# MCU152A_USB_and_Power.net
KiCad netlist of a schematic drawn in Altium Designer
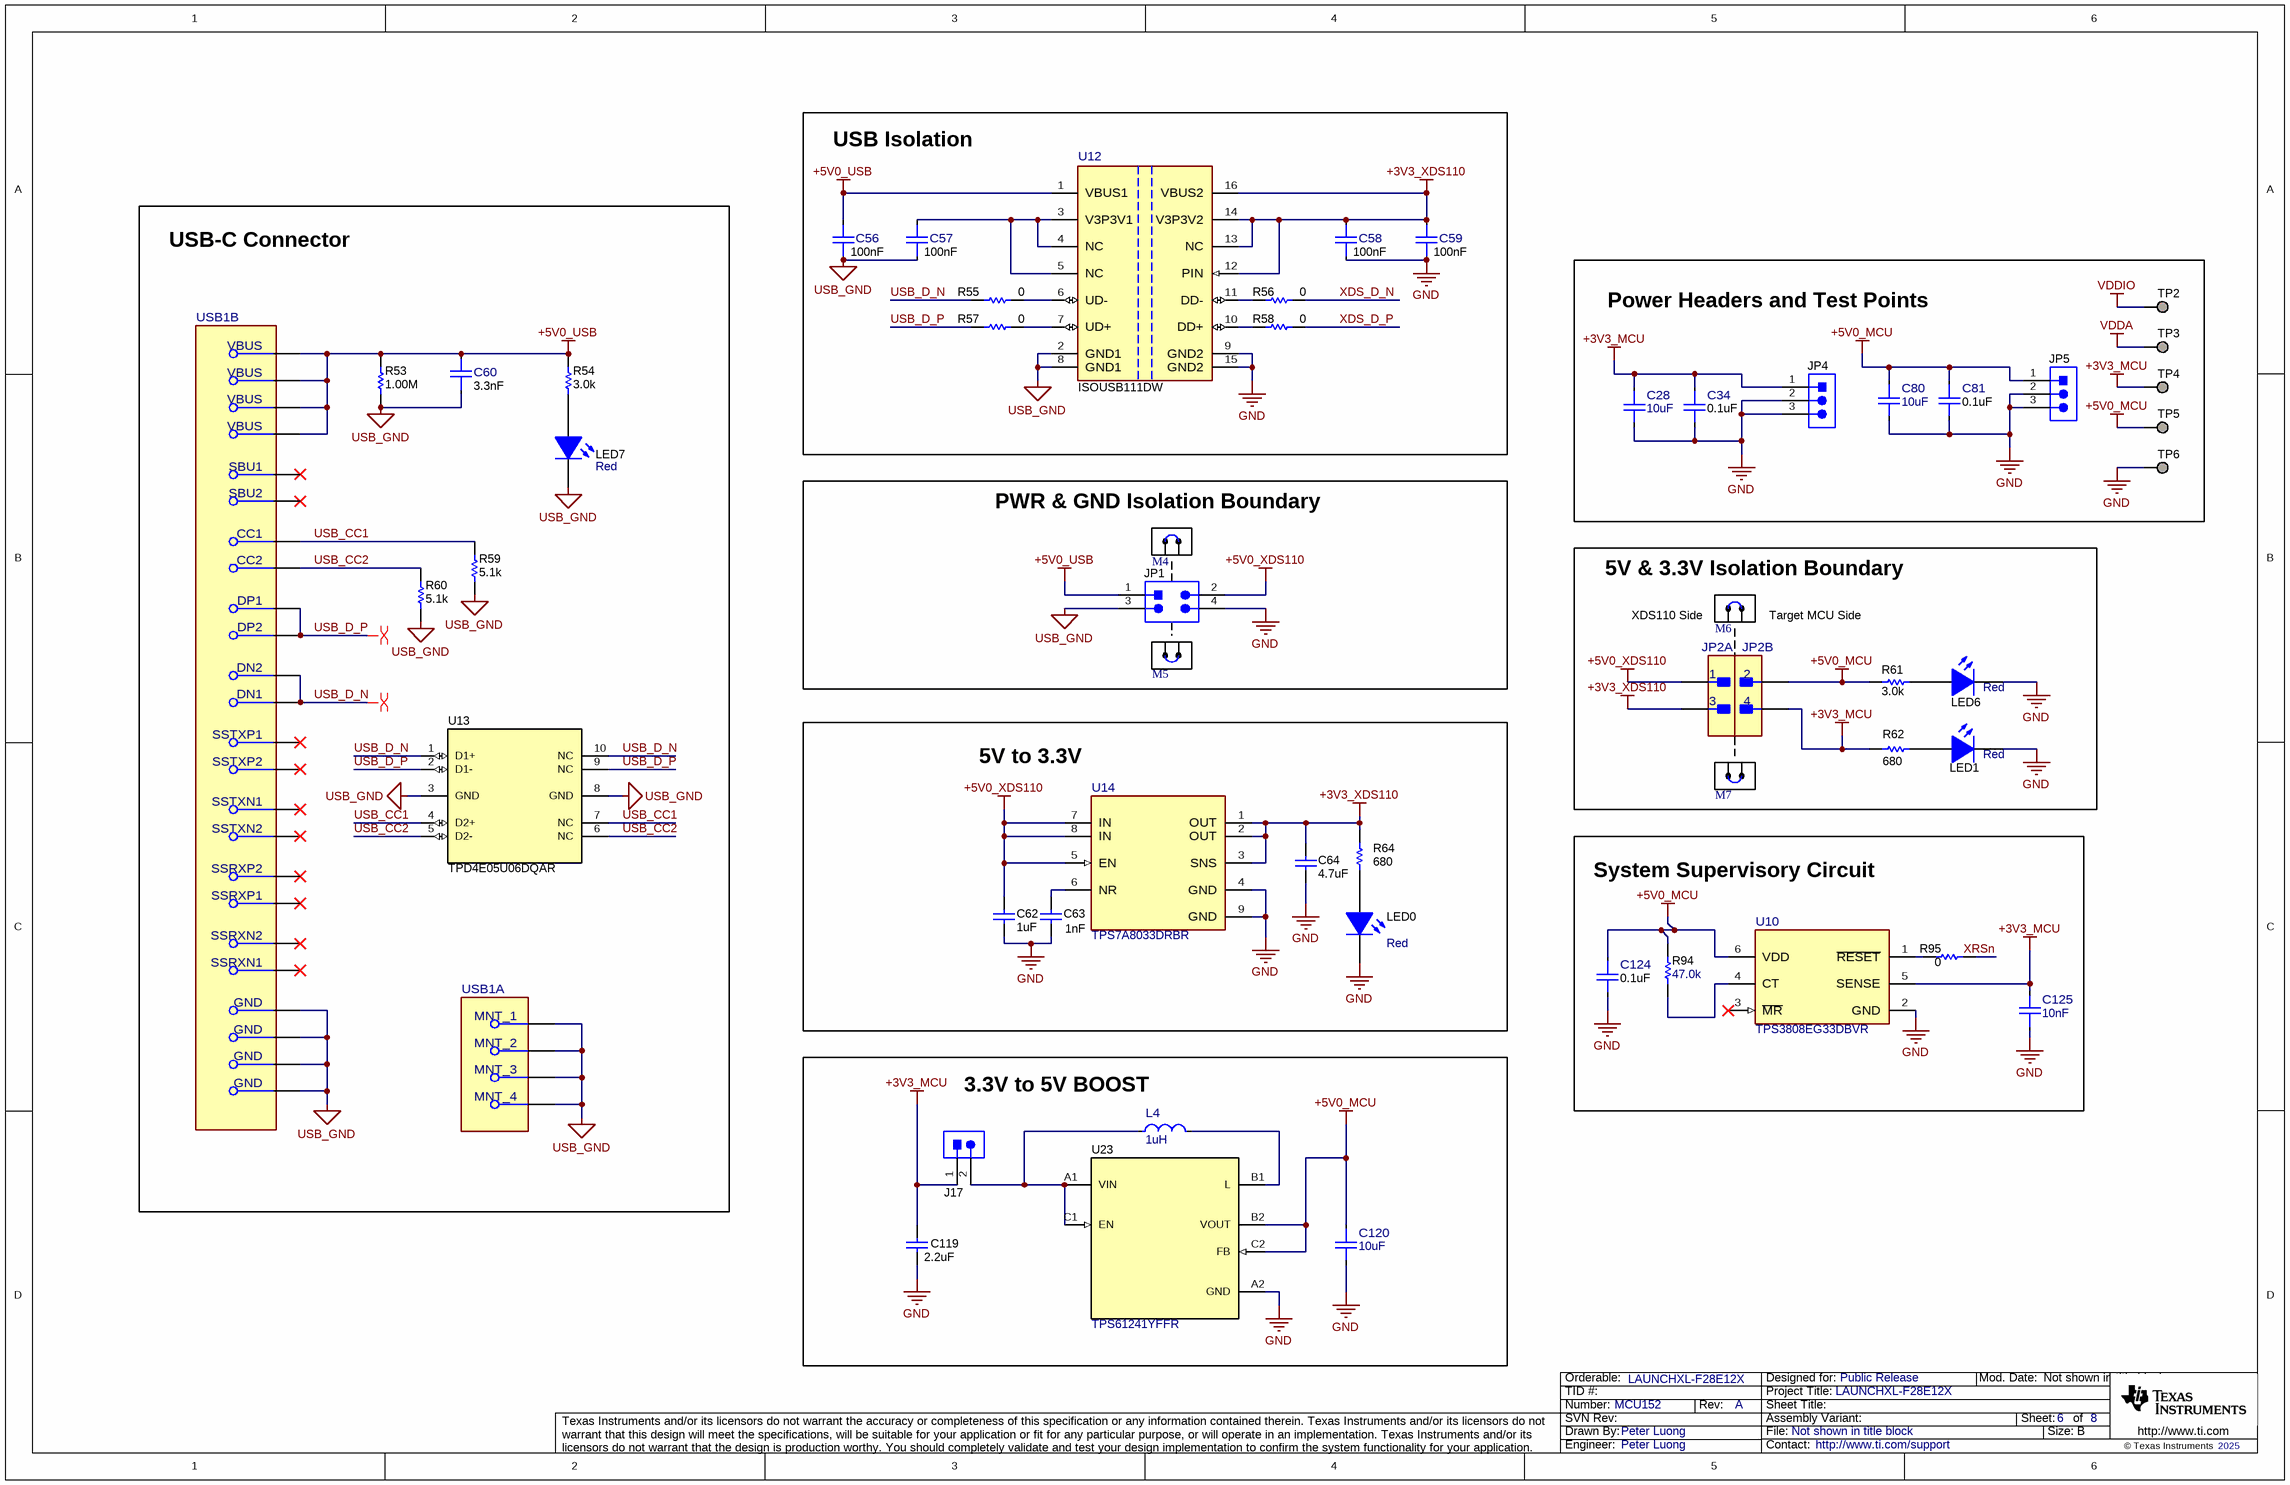
[diagram p0: MCU152A_USB_and_Power.SchDoc]

(export (version "E")
  (design (tool "Eeschema 10.0.6"))
  (components
    (comp (ref "C28")
      (value "885012106031")
      (footprint "FP-885012106031_0603-MFG")
      (description "10 µF ±20% 25V Ceramic Capacitor X5R 0603 (1608 Metric)")
      (fields (field (name "MANUFACTURER") "Wurth") (field (name "VALUEDISPLAYED") "10uF"))
      (libsource (lib "Altium Vault - TI") (part "SYM-885012106031"))
    )
    (comp (ref "C34")
      (value "885012205018")
      (footprint "FP-885012205018_0402-MFG")
      (description "0.1µF ±10% 10V Ceramic Capacitor X7R 0402 (1005 Metric)")
      (fields
        (field (name "MANUFACTURER") "Wurth Electronics")
        (field (name "MOUSER PART NUMBER") "710-885012205018")
        (field (name "VALUEDISPLAYED") "0.1uF")
      )
      (libsource (lib "Altium Vault - TI") (part "SYM-885012205018"))
    )
    (comp (ref "C56")
      (value "885012205018")
      (footprint "FP-885012205018_0402-MFG")
      (description "0.1µF ±10% 10V Ceramic Capacitor X7R 0402 (1005 Metric)")
      (fields
        (field (name "MANUFACTURER") "Wurth Electronics")
        (field (name "MOUSER PART NUMBER") "710-885012205018")
        (field (name "CAP_F") "100nF")
      )
      (libsource (lib "Altium Vault - TI") (part "SYM-885012205018"))
    )
    (comp (ref "C57")
      (value "885012205018")
      (footprint "FP-885012205018_0402-MFG")
      (description "0.1µF ±10% 10V Ceramic Capacitor X7R 0402 (1005 Metric)")
      (fields
        (field (name "MANUFACTURER") "Wurth Electronics")
        (field (name "MOUSER PART NUMBER") "710-885012205018")
        (field (name "CAP_F") "100nF")
      )
      (libsource (lib "Altium Vault - TI") (part "SYM-885012205018"))
    )
    (comp (ref "C58")
      (value "885012205018")
      (footprint "FP-885012205018_0402-MFG")
      (description "0.1µF ±10% 10V Ceramic Capacitor X7R 0402 (1005 Metric)")
      (fields
        (field (name "MANUFACTURER") "Wurth Electronics")
        (field (name "MOUSER PART NUMBER") "710-885012205018")
        (field (name "CAP_F") "100nF")
      )
      (libsource (lib "Altium Vault - TI") (part "SYM-885012205018"))
    )
    (comp (ref "C59")
      (value "885012205018")
      (footprint "FP-885012205018_0402-MFG")
      (description "0.1µF ±10% 10V Ceramic Capacitor X7R 0402 (1005 Metric)")
      (fields
        (field (name "MANUFACTURER") "Wurth Electronics")
        (field (name "MOUSER PART NUMBER") "710-885012205018")
        (field (name "CAP_F") "100nF")
      )
      (libsource (lib "Altium Vault - TI") (part "SYM-885012205018"))
    )
    (comp (ref "C60")
      (value "885012205064")
      (footprint "FP-885012205064_0402-MFG")
      (description "Cap Cer 3300pF 50V X7R 0402")
      (fields
        (field (name "MANUFACTURER") "Wurth Electronics")
        (field (name "DIGIKEY PART NUMBER") "732-7559-1-ND")
        (field (name "VALUEDISPLAYED") "3.3nF")
      )
      (libsource (lib "Altium Vault - TI") (part "SYM-885012205064"))
    )
    (comp (ref "C62")
      (value "885012105012")
      (footprint "0402")
      (description "CAP, CERM, 1 uF, 10 V,+/- 20%, X5R, 0402")
      (fields
        (field (name "VALUEDISPLAYED") "1uF")
        (field (name "MANUFACTURER") "Wurth Elektronik")
        (field (name "PUBLISHER") "Texas Instruments")
      )
      (libsource (lib "Altium Vault - TI") (part "Capacitor"))
    )
    (comp (ref "C63")
      (value "885012205061")
      (footprint "0402")
      (description "CAP, CERM, 1000 pF, 50 V, +/- 10%, X7R, 0402")
      (fields
        (field (name "MANUFACTURER") "Wurth Elektronik")
        (field (name "CAP_F") "1nF")
        (field (name "PUBLISHER") "Texas Instruments")
      )
      (libsource (lib "Altium Vault - TI") (part "Capacitor"))
    )
    (comp (ref "C64")
      (value "C1005X5R1A475K050BC")
      (footprint "0402_065")
      (description "CAP, CERM, 4.7 uF, 10 V, +/- 10%, X5R, 0402")
      (fields
        (field (name "MANUFACTURER") "TDK")
        (field (name "VALUEDISPLAYED") "4.7uF")
        (field (name "PUBLISHER") "Texas Instruments")
      )
      (libsource (lib "Altium Vault - TI") (part "Capacitor"))
    )
    (comp (ref "C80")
      (value "885012106031")
      (footprint "FP-885012106031_0603-MFG")
      (description "10 µF ±20% 25V Ceramic Capacitor X5R 0603 (1608 Metric)")
      (fields (field (name "MANUFACTURER") "Wurth") (field (name "VALUEDISPLAYED") "10uF"))
      (libsource (lib "Altium Vault - TI") (part "SYM-885012106031"))
    )
    (comp (ref "C81")
      (value "885012205018")
      (footprint "FP-885012205018_0402-MFG")
      (description "0.1µF ±10% 10V Ceramic Capacitor X7R 0402 (1005 Metric)")
      (fields
        (field (name "MANUFACTURER") "Wurth Electronics")
        (field (name "MOUSER PART NUMBER") "710-885012205018")
        (field (name "VALUEDISPLAYED") "0.1uF")
      )
      (libsource (lib "Altium Vault - TI") (part "SYM-885012205018"))
    )
    (comp (ref "C119")
      (value "885012106018")
      (footprint "0603")
      (description "CAP, CERM, 2.2 uF, 16 V, +/- 20%, X5R, 0603")
      (fields
        (field (name "MANUFACTURER") "Wurth Elektronik")
        (field (name "VALUEDISPLAYED") "2.2uF")
        (field (name "PUBLISHER") "Texas Instruments")
      )
      (libsource (lib "Altium Vault - TI") (part "Capacitor"))
    )
    (comp (ref "C120")
      (value "885012106031")
      (footprint "FP-885012106031_0603-MFG")
      (description "10 µF ±20% 25V Ceramic Capacitor X5R 0603 (1608 Metric)")
      (fields (field (name "MANUFACTURER") "Wurth") (field (name "VALUEDISPLAYED") "10uF"))
      (libsource (lib "Altium Vault - TI") (part "SYM-885012106031"))
    )
    (comp (ref "C124")
      (value "885012205018")
      (footprint "FP-885012205018_0402-MFG")
      (description "0.1µF ±10% 10V Ceramic Capacitor X7R 0402 (1005 Metric)")
      (fields
        (field (name "MANUFACTURER") "Wurth Electronics")
        (field (name "MOUSER PART NUMBER") "710-885012205018")
        (field (name "VALUEDISPLAYED") "0.1uF")
      )
      (libsource (lib "Altium Vault - TI") (part "SYM-885012205018"))
    )
    (comp (ref "C125")
      (value "885012206040")
      (footprint "FP-885012206040_0603-MFG")
      (description "10000 pF ±10% 16V Ceramic Capacitor X7R 0603 (1608 Metric)")
      (fields
        (field (name "CAP_F") "10nF")
        (field (name "MANUFACTURER") "Wurth")
        (field (name "DIGIKEY PART NUMBER") "732-7959-1-ND")
      )
      (libsource (lib "Altium Vault - TI") (part "SYM-885012206040"))
    )
    (comp (ref "J17")
      (value "61300211121")
      (footprint "WURTH_61300211121")
      (description "Header, 2.54 mm, 2x1, Gold, TH")
      (fields (field (name "MANUFACTURER") "Wurth Elektronik"))
      (libsource (lib "Altium Vault - TI") (part "Header_2x1"))
    )
    (comp (ref "JP1")
      (value "TSM-102-01-L-DV")
      (footprint "Samtec_TSM-102-01-x-DV")
      (description "Header, 2.54mm, 2x2, Gold, SMT")
      (fields (field (name "MANUFACTURER") "Samtec") (field (name "PUBLISHER") "Texas Instruments"))
      (libsource (lib "Altium Vault - TI") (part "Header_2x2"))
    )
    (comp (ref "JP2")
      (value "61300421121")
      (footprint "FP-61300421121_HDR4-MFG")
      (description "THT Vertical Pin Header WR-PHD, Pitch 2.54 mm, Dual Row, 4 pins")
      (fields
        (field (name "MANUFACTURER") "Wurth Electronics")
        (field (name "MOUSER PART NUMBER") "710-61300421121")
      )
      (libsource (lib "Altium Vault - TI") (part "SYM-61300421121"))
    )
    (comp (ref "JP4")
      (value "61300311121")
      (footprint "WURTH_61300311121")
      (description "Header, 2.54 mm, 3x1, Gold, TH")
      (fields (field (name "MANUFACTURER") "Wurth Elektronik") (field (name "PUBLISHER") "Texas Instruments"))
      (libsource (lib "Altium Vault - TI") (part "Header_3x1"))
    )
    (comp (ref "JP5")
      (value "61300311121")
      (footprint "WURTH_61300311121")
      (description "Header, 2.54 mm, 3x1, Gold, TH")
      (fields (field (name "MANUFACTURER") "Wurth Elektronik") (field (name "PUBLISHER") "Texas Instruments"))
      (libsource (lib "Altium Vault - TI") (part "Header_3x1"))
    )
    (comp (ref "L4")
      (value "1uH")
      (footprint "FP-74479773210_0805-MFG")
      (fields
        (field (name "MANUFACTURER") "Wurth")
        (field (name "PARTNUMBER") "74479773210")
        (field (name "DIGIKEY PART NUMBER") "732-5056-1-ND")
      )
      (libsource (lib "Altium Vault - TI") (part "SYM-74479773210"))
    )
    (comp (ref "LED0")
      (value "Red")
      (footprint "WL-SMCW_RED_0805")
      (description "LED, Red, SMD")
      (fields (field (name "MANUFACTURER") "Wurth Elektronik") (field (name "PARTNUMBER") "150080SS75000"))
      (libsource (lib "Altium Vault - TI") (part "LED_A2_K1"))
    )
    (comp (ref "LED1")
      (value "Red")
      (footprint "WL-SMCW_RED_0805")
      (description "LED, Red, SMD")
      (fields (field (name "MANUFACTURER") "Wurth Elektronik") (field (name "PARTNUMBER") "150080SS75000"))
      (libsource (lib "Altium Vault - TI") (part "LED_A2_K1"))
    )
    (comp (ref "LED6")
      (value "Red")
      (footprint "WL-SMCW_RED_0805")
      (description "LED, Red, SMD")
      (fields (field (name "MANUFACTURER") "Wurth Elektronik") (field (name "PARTNUMBER") "150080SS75000"))
      (libsource (lib "Altium Vault - TI") (part "LED_A2_K1"))
    )
    (comp (ref "LED7")
      (value "Red")
      (footprint "WL-SMCW_RED_0805")
      (description "LED, Red, SMD")
      (fields (field (name "MANUFACTURER") "Wurth Elektronik") (field (name "PARTNUMBER") "150080SS75000"))
      (libsource (lib "Altium Vault - TI") (part "LED_A2_K1"))
    )
    (comp (ref "M4")
      (value "60900213421")
      (footprint "Wurth_60900213421")
      (description "Shunt, 2.54mm, Gold, Black")
      (fields (field (name "MANUFACTURER") "Wurth Elektronik"))
      (libsource (lib "") (part "Shunt_1"))
    )
    (comp (ref "M5")
      (value "60900213421")
      (footprint "Wurth_60900213421")
      (description "Shunt, 2.54mm, Gold, Black")
      (fields (field (name "MANUFACTURER") "Wurth Elektronik"))
      (libsource (lib "Altium Vault - TI") (part "Shunt"))
    )
    (comp (ref "M6")
      (value "60900213421")
      (footprint "Wurth_60900213421")
      (description "Shunt, 2.54mm, Gold, Black")
      (fields (field (name "MANUFACTURER") "Wurth Elektronik"))
      (libsource (lib "") (part "Shunt_1"))
    )
    (comp (ref "M7")
      (value "60900213421")
      (footprint "Wurth_60900213421")
      (description "Shunt, 2.54mm, Gold, Black")
      (fields (field (name "MANUFACTURER") "Wurth Elektronik"))
      (libsource (lib "Altium Vault - TI") (part "Shunt"))
    )
    (comp (ref "R53")
      (value "CRCW04021M00FKED")
      (footprint "0402")
      (description "RES, 1.00 M, 1%, 0.063 W, AEC-Q200 Grade 0, 0402")
      (fields (field (name "VALUEDISPLAYED") "1.00M") (field (name "MANUFACTURER") "Vishay-Dale"))
      (libsource (lib "Altium Vault - TI") (part "Resistor"))
    )
    (comp (ref "R54")
      (value "RC0603JR-073KL")
      (footprint "0603")
      (description "RES, 3.0 k, 5%, 0.1 W, 0603")
      (fields (field (name "MANUFACTURER") "Yageo") (field (name "VALUEDISPLAYED") "3.0k"))
      (libsource (lib "Altium Vault - TI") (part "Resistor"))
    )
    (comp (ref "R55")
      (value "RC0402JR-070RL")
      (footprint "0402")
      (description "RES, 0, 5%, 0.063 W, 0402")
      (fields
        (field (name "MANUFACTURER") "Yageo America")
        (field (name "VALUEDISPLAYED") "0")
        (field (name "PUBLISHER") "Texas Instruments")
      )
      (libsource (lib "Altium Vault - TI") (part "Resistor"))
    )
    (comp (ref "R56")
      (value "RC0402JR-070RL")
      (footprint "0402")
      (description "RES, 0, 5%, 0.063 W, 0402")
      (fields
        (field (name "MANUFACTURER") "Yageo America")
        (field (name "VALUEDISPLAYED") "0")
        (field (name "PUBLISHER") "Texas Instruments")
      )
      (libsource (lib "Altium Vault - TI") (part "Resistor"))
    )
    (comp (ref "R57")
      (value "RC0402JR-070RL")
      (footprint "0402")
      (description "RES, 0, 5%, 0.063 W, 0402")
      (fields
        (field (name "MANUFACTURER") "Yageo America")
        (field (name "VALUEDISPLAYED") "0")
        (field (name "PUBLISHER") "Texas Instruments")
      )
      (libsource (lib "Altium Vault - TI") (part "Resistor"))
    )
    (comp (ref "R58")
      (value "RC0402JR-070RL")
      (footprint "0402")
      (description "RES, 0, 5%, 0.063 W, 0402")
      (fields
        (field (name "MANUFACTURER") "Yageo America")
        (field (name "VALUEDISPLAYED") "0")
        (field (name "PUBLISHER") "Texas Instruments")
      )
      (libsource (lib "Altium Vault - TI") (part "Resistor"))
    )
    (comp (ref "R59")
      (value "RC0603JR-075K1L")
      (footprint "0603")
      (description "RES, 5.1 k, 5%, 0.1 W, 0603")
      (fields (field (name "MANUFACTURER") "Yageo") (field (name "VALUEDISPLAYED") "5.1k"))
      (libsource (lib "Altium Vault - TI") (part "Resistor"))
    )
    (comp (ref "R60")
      (value "RC0603JR-075K1L")
      (footprint "0603")
      (description "RES, 5.1 k, 5%, 0.1 W, 0603")
      (fields (field (name "MANUFACTURER") "Yageo") (field (name "VALUEDISPLAYED") "5.1k"))
      (libsource (lib "Altium Vault - TI") (part "Resistor"))
    )
    (comp (ref "R61")
      (value "RC0603JR-073KL")
      (footprint "0603")
      (description "RES, 3.0 k, 5%, 0.1 W, 0603")
      (fields (field (name "MANUFACTURER") "Yageo") (field (name "VALUEDISPLAYED") "3.0k"))
      (libsource (lib "Altium Vault - TI") (part "Resistor"))
    )
    (comp (ref "R62")
      (value "CRCW0402680RJNED")
      (footprint "0402")
      (description "RES, 680, 5%, 0.063 W, AEC-Q200 Grade 0, 0402")
      (fields (field (name "MANUFACTURER") "Vishay-Dale") (field (name "VALUEDISPLAYED") "680"))
      (libsource (lib "Altium Vault - TI") (part "Resistor"))
    )
    (comp (ref "R64")
      (value "CRCW0402680RJNED")
      (footprint "0402")
      (description "RES, 680, 5%, 0.063 W, AEC-Q200 Grade 0, 0402")
      (fields (field (name "MANUFACTURER") "Vishay-Dale") (field (name "VALUEDISPLAYED") "680"))
      (libsource (lib "Altium Vault - TI") (part "Resistor"))
    )
    (comp (ref "R94")
      (value "RC0603FR-0747KL")
      (footprint "0603")
      (description "RES, 47.0 k, 1%, 0.1 W, 0603")
      (fields (field (name "MANUFACTURER") "Yageo") (field (name "VALUEDISPLAYED") "47.0k"))
      (libsource (lib "Altium Vault - TI") (part "Resistor"))
    )
    (comp (ref "R95")
      (value "ERJ-3GEY0R00V")
      (footprint "0603")
      (description "RES, 0, 5%, 0.1 W, AEC-Q200 Grade 0, 0603")
      (fields (field (name "MANUFACTURER") "Panasonic") (field (name "VALUEDISPLAYED") "0"))
      (libsource (lib "Altium Vault - TI") (part "Resistor"))
    )
    (comp (ref "TP2")
      (value "TESTPOINT")
      (footprint "TP_50MIL-25MILHOLE")
      (description "TEST POINT.  No entry in BOM.")
      (libsource (lib "Altium Vault - TI") (part "TESTPOINT"))
    )
    (comp (ref "TP3")
      (value "TESTPOINT")
      (footprint "TP_50MIL-25MILHOLE")
      (description "TEST POINT.  No entry in BOM.")
      (libsource (lib "Altium Vault - TI") (part "TESTPOINT"))
    )
    (comp (ref "TP4")
      (value "TESTPOINT")
      (footprint "TP_50MIL-25MILHOLE")
      (description "TEST POINT.  No entry in BOM.")
      (libsource (lib "Altium Vault - TI") (part "TESTPOINT"))
    )
    (comp (ref "TP5")
      (value "TESTPOINT")
      (footprint "TP_50MIL-25MILHOLE")
      (description "TEST POINT.  No entry in BOM.")
      (libsource (lib "Altium Vault - TI") (part "TESTPOINT"))
    )
    (comp (ref "TP6")
      (value "TESTPOINT")
      (footprint "TP_50MIL-25MILHOLE")
      (description "TEST POINT.  No entry in BOM.")
      (libsource (lib "Altium Vault - TI") (part "TESTPOINT"))
    )
    (comp (ref "U10")
      (value "TPS3808EG33DBVR")
      (footprint "DBV0006A-MFG")
      (description "Low-quiescent current supervisor with programmable delay and manual reset 6-SOT-23 -40 to 85")
      (fields (field (name "MANUFACTURER") "Texas Instruments") (field (name "PARTNUMBER") "TPS3808EG33DBVR"))
      (libsource (lib "Altium Vault - TI") (part "SYM-TPS3808EG33DBVR"))
    )
    (comp (ref "U12")
      (value "ISOUSB111DW")
      (footprint "DW0016B-MFG")
      (description "Full/Low Speed Isolated USB Repeater, SOIC16-Wide")
      (fields (field (name "MANUFACTURER") "Texas Instruments") (field (name "PARTNUMBER") "ISOUSB111DW"))
      (libsource (lib "Altium Vault - TI") (part "SYM-ISOUSB111DW"))
    )
    (comp (ref "U13")
      (value "TPD4E05U06DQAR")
      (footprint "DQA0010A")
      (description "4-Channel Ultra-Low-Capacitance IEC ESD Protection Diode, DQA0010A (USON-10)")
      (fields (field (name "MANUFACTURER") "Texas Instruments") (field (name "PARTNUMBER") "TPD4E05U06DQAR"))
      (libsource (lib "Altium Vault - TI") (part "TPD4E05U06"))
    )
    (comp (ref "U14")
      (value "TPS7A8033DRBR")
      (footprint "DRB0008A-MFG")
      (description "Low-Noise, Wide-Bandwidth, High PSRR, Low-Dropout 1-A Linear Regulator")
      (fields
        (field (name "MANUFACTURER") "Texas Instruments")
        (field (name "PARTNUMBER") "TPS7A8033DRBR")
        (field (name "DIGIKEY PART NUMBER") "296-52139-1-ND")
      )
      (libsource (lib "Altium Vault - TI") (part "SYM-TPS7A8033DRBR"))
    )
    (comp (ref "U23")
      (value "TPS61241YFFR")
      (footprint "YFF0006AEAE")
      (description "5V, 500mA, 4MHz Step-Up DC/DC Converter, YFF0006AEAE (DSBGA-6)")
      (fields
        (field (name "PARTNUMBER") "TPS61241YFFR")
        (field (name "ALTERNATE PARTNUMBER") "TPS61241YFFT")
        (field (name "MANUFACTURER") "Texas Instruments")
      )
      (libsource (lib "Altium Vault - TI") (part "TPS6124xYFF"))
    )
    (comp (ref "USB1")
      (value "MUP-U22001")
      (footprint "FP-MUP-U22001_CONN_USB_8MM94_8MM0-MFG")
      (description "Connector, USB Type-C 24 pin Mid Mount dual row Receptacle Surface Mount")
      (fields (field (name "MANUFACTURER") "MUP"))
      (libsource (lib "Altium Vault - TI") (part "SYM-MUP-U22001"))
    )
  )
  (nets
    (net (code "1") (name "+3V3_MCU") (class "Default")
      (node (ref "C119") (pin "1") (pinfunction "1_1") (pintype "passive"))
      (node (ref "C125") (pin "2") (pinfunction "2_2") (pintype "passive"))
      (node (ref "C28") (pin "1") (pinfunction "1_1") (pintype "passive"))
      (node (ref "C34") (pin "1") (pinfunction "1_1") (pintype "passive"))
      (node (ref "J17") (pin "1") (pinfunction "1_1") (pintype "passive"))
      (node (ref "JP2") (pin "4") (pinfunction "4_4") (pintype "passive"))
      (node (ref "JP4") (pin "1") (pinfunction "1_1") (pintype "passive"))
      (node (ref "R62") (pin "2") (pinfunction "2_2") (pintype "passive"))
      (node (ref "TP4") (pin "1") (pintype "passive"))
      (node (ref "U10") (pin "5") (pinfunction "SENSE_5") (pintype "passive"))
    )
    (net (code "2") (name "+3V3_XDS110") (class "Default")
      (node (ref "C58") (pin "2") (pinfunction "2_2") (pintype "passive"))
      (node (ref "C59") (pin "2") (pinfunction "2_2") (pintype "passive"))
      (node (ref "C64") (pin "1") (pinfunction "1_1") (pintype "passive"))
      (node (ref "JP2") (pin "3") (pinfunction "3_3") (pintype "passive"))
      (node (ref "R64") (pin "2") (pinfunction "2_2") (pintype "passive"))
      (node (ref "U12") (pin "12") (pinfunction "PIN_12") (pintype "input"))
      (node (ref "U12") (pin "13") (pinfunction "NC_13") (pintype "passive"))
      (node (ref "U12") (pin "14") (pinfunction "V3P3V2_14") (pintype "power_in"))
      (node (ref "U12") (pin "16") (pinfunction "VBUS2_16") (pintype "power_in"))
      (node (ref "U14") (pin "1") (pinfunction "OUT_1") (pintype "passive"))
      (node (ref "U14") (pin "2") (pinfunction "OUT_2") (pintype "passive"))
      (node (ref "U14") (pin "3") (pinfunction "SNS_3") (pintype "passive"))
    )
    (net (code "3") (name "+5V0_MCU") (class "Default")
      (node (ref "C120") (pin "1") (pinfunction "1_1") (pintype "passive"))
      (node (ref "C124") (pin "1") (pinfunction "1_1") (pintype "passive"))
      (node (ref "C80") (pin "1") (pinfunction "1_1") (pintype "passive"))
      (node (ref "C81") (pin "1") (pinfunction "1_1") (pintype "passive"))
      (node (ref "JP2") (pin "2") (pinfunction "2_2") (pintype "passive"))
      (node (ref "JP5") (pin "1") (pinfunction "1_1") (pintype "passive"))
      (node (ref "R61") (pin "2") (pinfunction "2_2") (pintype "passive"))
      (node (ref "R94") (pin "2") (pinfunction "2_2") (pintype "passive"))
      (node (ref "TP5") (pin "1") (pintype "passive"))
      (node (ref "U10") (pin "6") (pinfunction "VDD_6") (pintype "power_in"))
      (node (ref "U23") (pin "B2") (pinfunction "VOUT_B2") (pintype "power_in"))
      (node (ref "U23") (pin "C2") (pinfunction "FB_C2") (pintype "input"))
    )
    (net (code "4") (name "+5V0_USB") (class "Default")
      (node (ref "C56") (pin "2") (pinfunction "2_2") (pintype "passive"))
      (node (ref "C60") (pin "2") (pinfunction "2_2") (pintype "passive"))
      (node (ref "JP1") (pin "1") (pinfunction "1_1") (pintype "passive"))
      (node (ref "R53") (pin "2") (pinfunction "2_2") (pintype "passive"))
      (node (ref "R54") (pin "2") (pinfunction "2_2") (pintype "passive"))
      (node (ref "U12") (pin "1") (pinfunction "VBUS1_1") (pintype "power_in"))
      (node (ref "USB1") (pin "A4") (pinfunction "VBUS_A4") (pintype "passive"))
      (node (ref "USB1") (pin "A9") (pinfunction "VBUS_A9") (pintype "passive"))
      (node (ref "USB1") (pin "B4") (pinfunction "VBUS_B4") (pintype "passive"))
      (node (ref "USB1") (pin "B9") (pinfunction "VBUS_B9") (pintype "passive"))
    )
    (net (code "5") (name "+5V0_XDS110") (class "Default")
      (node (ref "C62") (pin "1") (pinfunction "1_1") (pintype "passive"))
      (node (ref "JP1") (pin "2") (pinfunction "2_2") (pintype "passive"))
      (node (ref "JP2") (pin "1") (pinfunction "1_1") (pintype "passive"))
      (node (ref "U14") (pin "5") (pinfunction "EN_5") (pintype "input"))
      (node (ref "U14") (pin "7") (pinfunction "IN_7") (pintype "power_in"))
      (node (ref "U14") (pin "8") (pinfunction "IN_8") (pintype "power_in"))
    )
    (net (code "6") (name "/USB_CC1") (class "Default")
      (node (ref "R59") (pin "2") (pinfunction "2_2") (pintype "passive"))
      (node (ref "U13") (pin "4") (pinfunction "D2+_4") (pintype "bidirectional"))
      (node (ref "U13") (pin "7") (pinfunction "NC_7") (pintype "passive"))
      (node (ref "USB1") (pin "A5") (pinfunction "CC1_A5") (pintype "passive"))
    )
    (net (code "7") (name "/USB_CC2") (class "Default")
      (node (ref "R60") (pin "2") (pinfunction "2_2") (pintype "passive"))
      (node (ref "U13") (pin "5") (pinfunction "D2-_5") (pintype "bidirectional"))
      (node (ref "U13") (pin "6") (pinfunction "NC_6") (pintype "passive"))
      (node (ref "USB1") (pin "B5") (pinfunction "CC2_B5") (pintype "passive"))
    )
    (net (code "8") (name "/USB_D_N") (class "Default")
      (node (ref "R55") (pin "1") (pinfunction "1_1") (pintype "passive"))
      (node (ref "U13") (pin "1") (pinfunction "D1+_1") (pintype "bidirectional"))
      (node (ref "U13") (pin "10") (pinfunction "NC_10") (pintype "passive"))
      (node (ref "USB1") (pin "A7") (pinfunction "DN1_A7") (pintype "passive"))
      (node (ref "USB1") (pin "B7") (pinfunction "DN2_B7") (pintype "passive"))
    )
    (net (code "9") (name "/USB_D_P") (class "Default")
      (node (ref "R57") (pin "1") (pinfunction "1_1") (pintype "passive"))
      (node (ref "U13") (pin "2") (pinfunction "D1-_2") (pintype "bidirectional"))
      (node (ref "U13") (pin "9") (pinfunction "NC_9") (pintype "passive"))
      (node (ref "USB1") (pin "A6") (pinfunction "DP1_A6") (pintype "passive"))
      (node (ref "USB1") (pin "B6") (pinfunction "DP2_B6") (pintype "passive"))
    )
    (net (code "10") (name "/XDS_D_N") (class "Default")
      (node (ref "R56") (pin "2") (pinfunction "2_2") (pintype "passive"))
    )
    (net (code "11") (name "/XDS_D_P") (class "Default")
      (node (ref "R58") (pin "2") (pinfunction "2_2") (pintype "passive"))
    )
    (net (code "12") (name "/XRSn") (class "Default")
      (node (ref "R95") (pin "1") (pinfunction "1_1") (pintype "passive"))
    )
    (net (code "13") (name "GND") (class "Default")
      (node (ref "C119") (pin "2") (pinfunction "2_2") (pintype "passive"))
      (node (ref "C120") (pin "2") (pinfunction "2_2") (pintype "passive"))
      (node (ref "C124") (pin "2") (pinfunction "2_2") (pintype "passive"))
      (node (ref "C125") (pin "1") (pinfunction "1_1") (pintype "passive"))
      (node (ref "C28") (pin "2") (pinfunction "2_2") (pintype "passive"))
      (node (ref "C34") (pin "2") (pinfunction "2_2") (pintype "passive"))
      (node (ref "C58") (pin "1") (pinfunction "1_1") (pintype "passive"))
      (node (ref "C59") (pin "1") (pinfunction "1_1") (pintype "passive"))
      (node (ref "C62") (pin "2") (pinfunction "2_2") (pintype "passive"))
      (node (ref "C63") (pin "2") (pinfunction "2_2") (pintype "passive"))
      (node (ref "C64") (pin "2") (pinfunction "2_2") (pintype "passive"))
      (node (ref "C80") (pin "2") (pinfunction "2_2") (pintype "passive"))
      (node (ref "C81") (pin "2") (pinfunction "2_2") (pintype "passive"))
      (node (ref "JP1") (pin "4") (pinfunction "4_4") (pintype "passive"))
      (node (ref "JP4") (pin "2") (pinfunction "2_2") (pintype "passive"))
      (node (ref "JP4") (pin "3") (pinfunction "3_3") (pintype "passive"))
      (node (ref "JP5") (pin "2") (pinfunction "2_2") (pintype "passive"))
      (node (ref "JP5") (pin "3") (pinfunction "3_3") (pintype "passive"))
      (node (ref "LED0") (pin "1") (pinfunction "K_1") (pintype "passive"))
      (node (ref "LED1") (pin "1") (pinfunction "K_1") (pintype "passive"))
      (node (ref "LED6") (pin "1") (pinfunction "K_1") (pintype "passive"))
      (node (ref "TP6") (pin "1") (pintype "passive"))
      (node (ref "U10") (pin "2") (pinfunction "GND_2") (pintype "power_in"))
      (node (ref "U12") (pin "15") (pinfunction "GND2_15") (pintype "power_in"))
      (node (ref "U12") (pin "9") (pinfunction "GND2_9") (pintype "power_in"))
      (node (ref "U14") (pin "4") (pinfunction "GND_4") (pintype "power_in"))
      (node (ref "U14") (pin "9") (pinfunction "GND_9") (pintype "power_in"))
      (node (ref "U23") (pin "A2") (pinfunction "GND_A2") (pintype "power_in"))
    )
    (net (code "14") (name "Net-(LED0-A)") (class "Default")
      (node (ref "LED0") (pin "2") (pinfunction "A_2") (pintype "passive"))
      (node (ref "R64") (pin "1") (pinfunction "1_1") (pintype "passive"))
    )
    (net (code "15") (name "Net-(LED1-A)") (class "Default")
      (node (ref "LED1") (pin "2") (pinfunction "A_2") (pintype "passive"))
      (node (ref "R62") (pin "1") (pinfunction "1_1") (pintype "passive"))
    )
    (net (code "16") (name "Net-(LED6-A)") (class "Default")
      (node (ref "LED6") (pin "2") (pinfunction "A_2") (pintype "passive"))
      (node (ref "R61") (pin "1") (pinfunction "1_1") (pintype "passive"))
    )
    (net (code "17") (name "Net-(LED7-A)") (class "Default")
      (node (ref "LED7") (pin "2") (pinfunction "A_2") (pintype "passive"))
      (node (ref "R54") (pin "1") (pinfunction "1_1") (pintype "passive"))
    )
    (net (code "18") (name "Net-(U10-CT)") (class "Default")
      (node (ref "R94") (pin "1") (pinfunction "1_1") (pintype "passive"))
      (node (ref "U10") (pin "4") (pinfunction "CT_4") (pintype "passive"))
    )
    (net (code "19") (name "Net-(U10-~{RESET})") (class "Default")
      (node (ref "R95") (pin "2") (pinfunction "2_2") (pintype "passive"))
      (node (ref "U10") (pin "1") (pinfunction "~{RESET}_1") (pintype "open_collector"))
    )
    (net (code "20") (name "Net-(U12-DD+)") (class "Default")
      (node (ref "R58") (pin "1") (pinfunction "1_1") (pintype "passive"))
      (node (ref "U12") (pin "10") (pinfunction "DD+_10") (pintype "bidirectional"))
    )
    (net (code "21") (name "Net-(U12-DD-)") (class "Default")
      (node (ref "R56") (pin "1") (pinfunction "1_1") (pintype "passive"))
      (node (ref "U12") (pin "11") (pinfunction "DD-_11") (pintype "bidirectional"))
    )
    (net (code "22") (name "Net-(U12-UD+)") (class "Default")
      (node (ref "R57") (pin "2") (pinfunction "2_2") (pintype "passive"))
      (node (ref "U12") (pin "7") (pinfunction "UD+_7") (pintype "bidirectional"))
    )
    (net (code "23") (name "Net-(U12-UD-)") (class "Default")
      (node (ref "R55") (pin "2") (pinfunction "2_2") (pintype "passive"))
      (node (ref "U12") (pin "6") (pinfunction "UD-_6") (pintype "bidirectional"))
    )
    (net (code "24") (name "Net-(U12-V3P3V1)") (class "Default")
      (node (ref "C57") (pin "2") (pinfunction "2_2") (pintype "passive"))
      (node (ref "U12") (pin "3") (pinfunction "V3P3V1_3") (pintype "power_in"))
      (node (ref "U12") (pin "4") (pinfunction "NC_4") (pintype "passive"))
      (node (ref "U12") (pin "5") (pinfunction "NC_5") (pintype "passive"))
    )
    (net (code "25") (name "Net-(U14-NR)") (class "Default")
      (node (ref "C63") (pin "1") (pinfunction "1_1") (pintype "passive"))
      (node (ref "U14") (pin "6") (pinfunction "NR_6") (pintype "passive"))
    )
    (net (code "26") (name "Net-(U23-EN)") (class "Default")
      (node (ref "J17") (pin "2") (pinfunction "2_2") (pintype "passive"))
      (node (ref "L4") (pin "1") (pinfunction "1_1") (pintype "passive"))
      (node (ref "U23") (pin "A1") (pinfunction "VIN_A1") (pintype "power_in"))
      (node (ref "U23") (pin "C1") (pinfunction "EN_C1") (pintype "input"))
    )
    (net (code "27") (name "Net-(U23-L)") (class "Default")
      (node (ref "L4") (pin "2") (pinfunction "2_2") (pintype "passive"))
      (node (ref "U23") (pin "B1") (pinfunction "L_B1") (pintype "passive"))
    )
    (net (code "28") (name "USB_GND") (class "Default")
      (node (ref "C56") (pin "1") (pinfunction "1_1") (pintype "passive"))
      (node (ref "C57") (pin "1") (pinfunction "1_1") (pintype "passive"))
      (node (ref "C60") (pin "1") (pinfunction "1_1") (pintype "passive"))
      (node (ref "JP1") (pin "3") (pinfunction "3_3") (pintype "passive"))
      (node (ref "LED7") (pin "1") (pinfunction "K_1") (pintype "passive"))
      (node (ref "R53") (pin "1") (pinfunction "1_1") (pintype "passive"))
      (node (ref "R59") (pin "1") (pinfunction "1_1") (pintype "passive"))
      (node (ref "R60") (pin "1") (pinfunction "1_1") (pintype "passive"))
      (node (ref "U12") (pin "2") (pinfunction "GND1_2") (pintype "power_in"))
      (node (ref "U12") (pin "8") (pinfunction "GND1_8") (pintype "power_in"))
      (node (ref "U13") (pin "3") (pinfunction "GND_3") (pintype "power_in"))
      (node (ref "U13") (pin "8") (pinfunction "GND_8") (pintype "power_in"))
      (node (ref "USB1") (pin "1") (pinfunction "MNT_1_1") (pintype "passive"))
      (node (ref "USB1") (pin "2") (pinfunction "MNT_2_2") (pintype "passive"))
      (node (ref "USB1") (pin "3") (pinfunction "MNT_3_3") (pintype "passive"))
      (node (ref "USB1") (pin "4") (pinfunction "MNT_4_4") (pintype "passive"))
      (node (ref "USB1") (pin "A1") (pinfunction "GND_A1") (pintype "passive"))
      (node (ref "USB1") (pin "A12") (pinfunction "GND_A12") (pintype "passive"))
      (node (ref "USB1") (pin "B1") (pinfunction "GND_B1") (pintype "passive"))
      (node (ref "USB1") (pin "B12") (pinfunction "GND_B12") (pintype "passive"))
    )
    (net (code "29") (name "VDDA") (class "Default") (node (ref "TP3") (pin "1") (pintype "passive")))
    (net (code "30") (name "VDDIO") (class "Default") (node (ref "TP2") (pin "1") (pintype "passive")))
    (net (code "31") (name "unconnected-(U10-~{MR}-Pad3)") (class "Default")
      (node (ref "U10") (pin "3") (pinfunction "~{MR}_3") (pintype "input+no_connect"))
    )
    (net (code "32") (name "unconnected-(USB1B-SBU1-PadA8)") (class "Default")
      (node (ref "USB1") (pin "A8") (pinfunction "SBU1_A8") (pintype "passive+no_connect"))
    )
    (net (code "33") (name "unconnected-(USB1B-SBU2-PadB8)") (class "Default")
      (node (ref "USB1") (pin "B8") (pinfunction "SBU2_B8") (pintype "passive+no_connect"))
    )
    (net (code "34") (name "unconnected-(USB1B-SSRXN1-PadB10)") (class "Default")
      (node (ref "USB1") (pin "B10") (pinfunction "SSRXN1_B10") (pintype "passive+no_connect"))
    )
    (net (code "35") (name "unconnected-(USB1B-SSRXN2-PadA10)") (class "Default")
      (node (ref "USB1") (pin "A10") (pinfunction "SSRXN2_A10") (pintype "passive+no_connect"))
    )
    (net (code "36") (name "unconnected-(USB1B-SSRXP1-PadB11)") (class "Default")
      (node (ref "USB1") (pin "B11") (pinfunction "SSRXP1_B11") (pintype "passive+no_connect"))
    )
    (net (code "37") (name "unconnected-(USB1B-SSRXP2-PadA11)") (class "Default")
      (node (ref "USB1") (pin "A11") (pinfunction "SSRXP2_A11") (pintype "passive+no_connect"))
    )
    (net (code "38") (name "unconnected-(USB1B-SSTXN1-PadA3)") (class "Default")
      (node (ref "USB1") (pin "A3") (pinfunction "SSTXN1_A3") (pintype "passive+no_connect"))
    )
    (net (code "39") (name "unconnected-(USB1B-SSTXN2-PadB3)") (class "Default")
      (node (ref "USB1") (pin "B3") (pinfunction "SSTXN2_B3") (pintype "passive+no_connect"))
    )
    (net (code "40") (name "unconnected-(USB1B-SSTXP1-PadA2)") (class "Default")
      (node (ref "USB1") (pin "A2") (pinfunction "SSTXP1_A2") (pintype "passive+no_connect"))
    )
    (net (code "41") (name "unconnected-(USB1B-SSTXP2-PadB2)") (class "Default")
      (node (ref "USB1") (pin "B2") (pinfunction "SSTXP2_B2") (pintype "passive+no_connect"))
    )
  )
)
